# mx8m_dram.net
KiCad netlist of a schematic drawn in Altium Designer
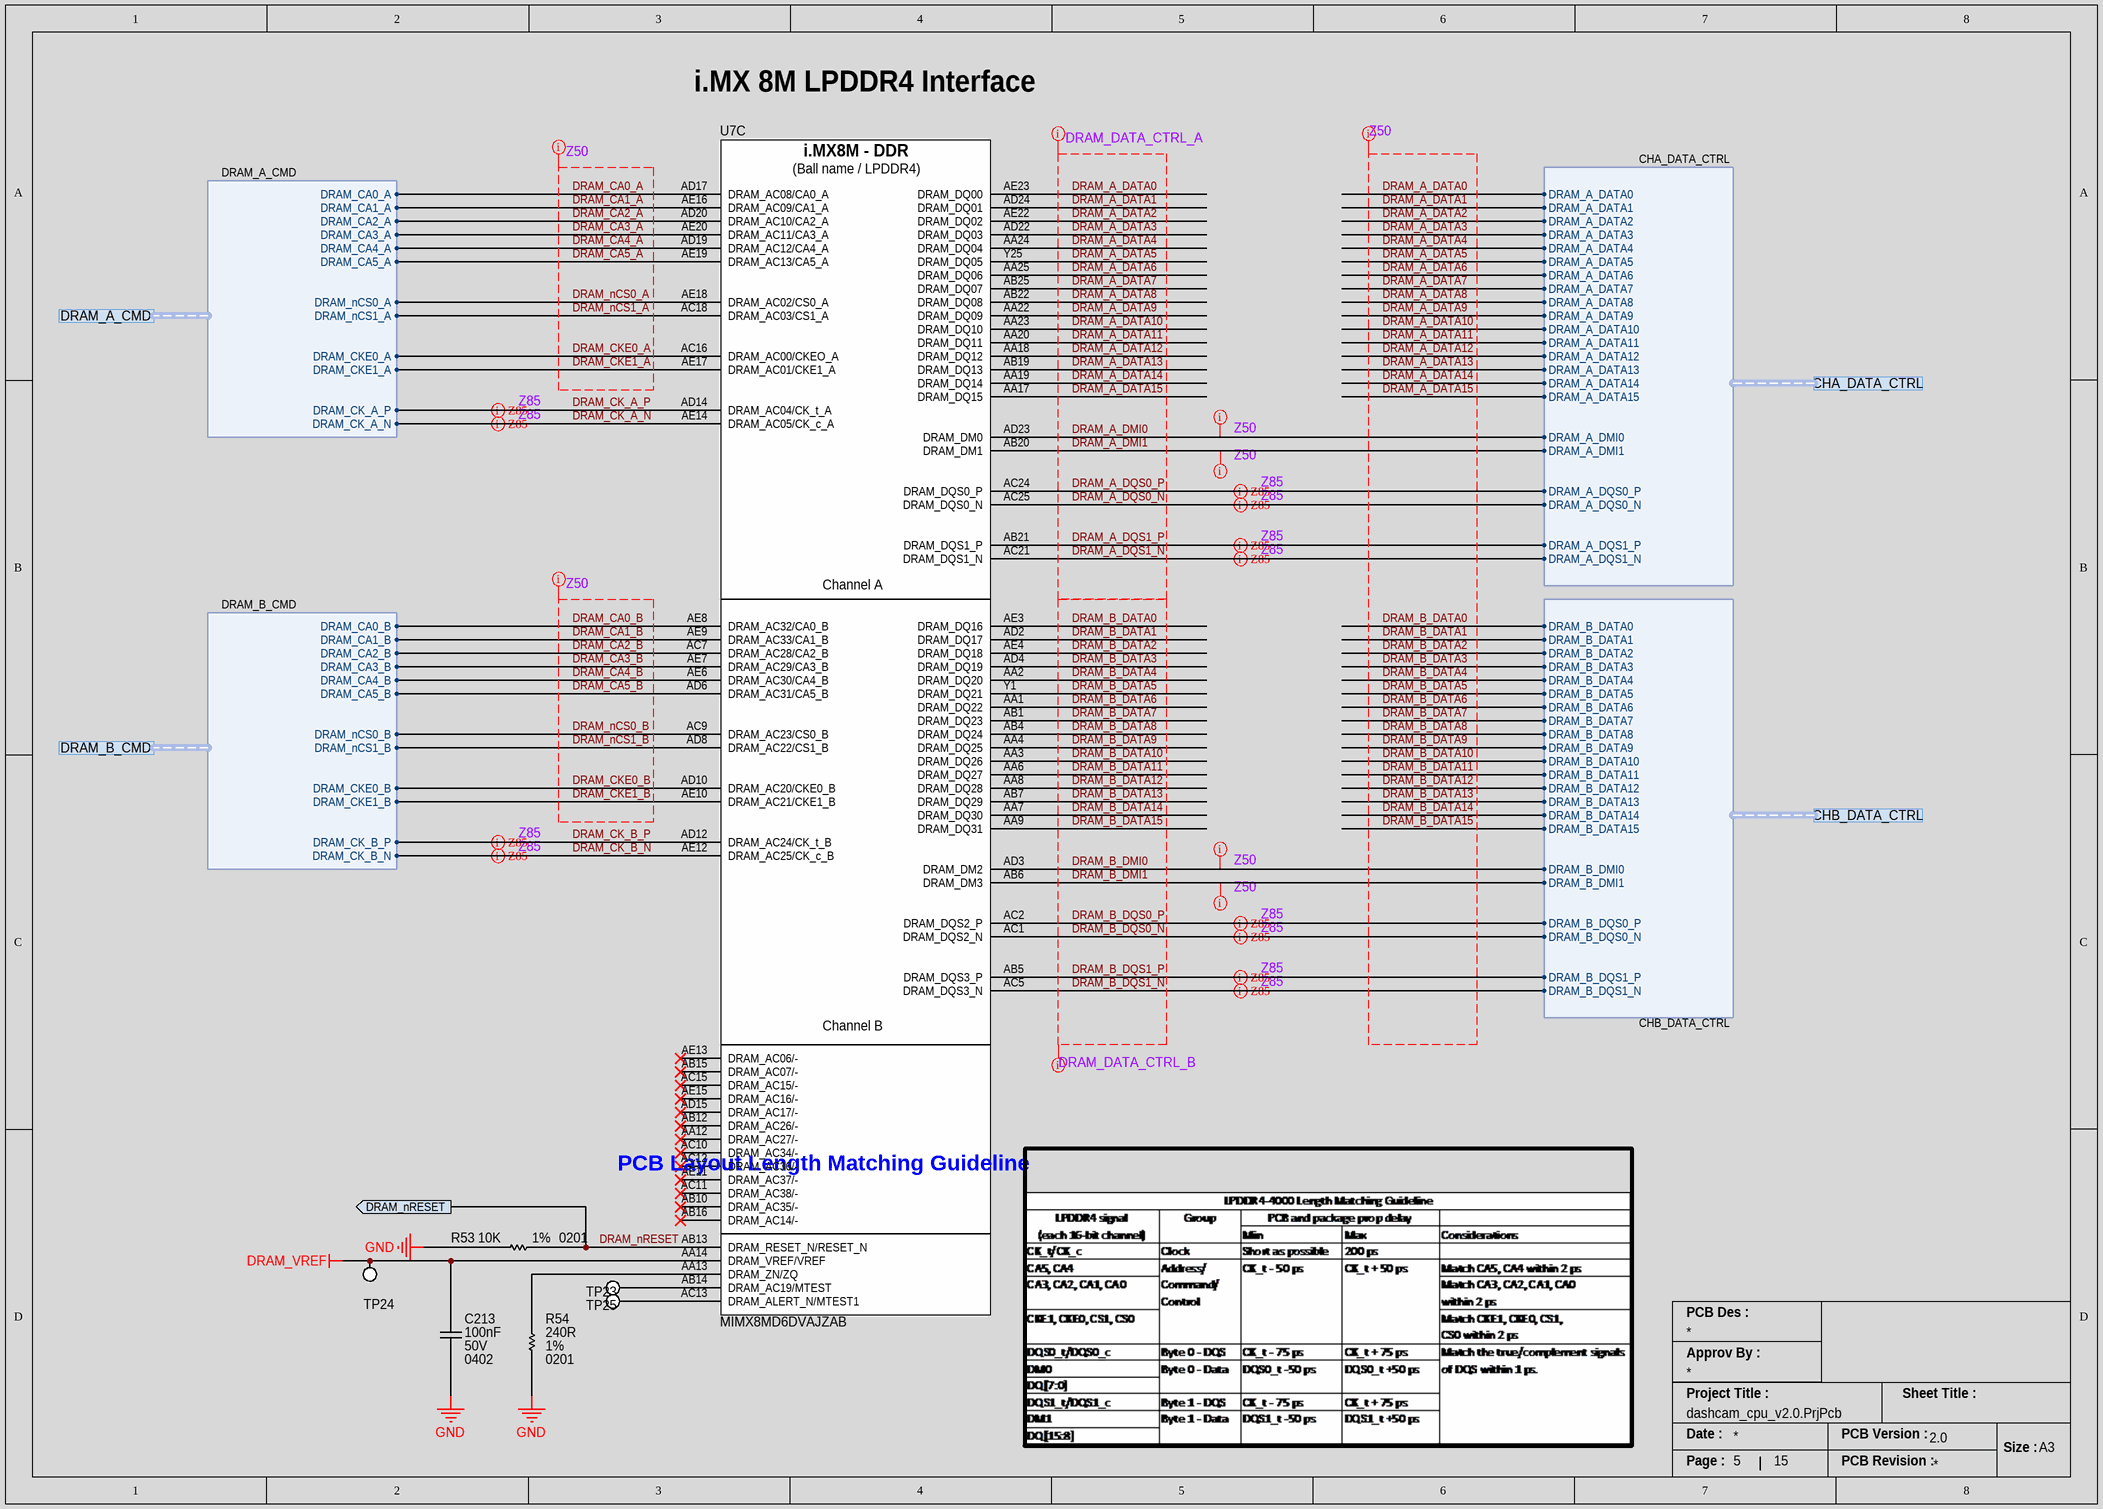
[diagram p0: mx8m_dram.SchDoc]

(export (version "E")
  (design (tool "Eeschema 10.0.6"))
  (components
    (comp (ref "C213")
      (value "GRM155R71H104KE14D")
      (footprint "CAP_0402_CAPC1005X05N")
      (description "Multilayer Ceramic Capacitor, 0.1 uF, 16 V, ± 10%, X7R, 0402 [1005 Metric]")
      (fields
        (field (name "MANUFACTURER") "Murata")
        (field (name "TOLERANCE") "10%")
        (field (name "VOLTAGE RATING") "50V")
        (field (name "CAPACITANCE") "100nF")
        (field (name "CASE/PACKAGE") "0402")
      )
      (libsource (lib "Electronic Devices_LIB") (part "CAP_100NF_50V_X7R_0402"))
    )
    (comp (ref "R53")
      (value "RC0201FR-0710KL")
      (footprint "RES_0201_RESC0603X02N")
      (description "SMD Chip Resistor, 10 kOhm, ± 1%, 50 mW, 0201 [0603 Metric], Thick Film, General Purpose")
      (fields
        (field (name "MANUFACTURER") "Yageo")
        (field (name "TOLERANCE") "1%")
        (field (name "RESISTANCE") "10K")
        (field (name "CASE CODE (IMPERIAL)") "0201")
      )
      (libsource (lib "Electronic Devices_LIB") (part "RES_10K_1/12W_1%_0201"))
    )
    (comp (ref "R54")
      (value "RC0201FR-07240RL")
      (footprint "RES_0201_RESC0603X02N")
      (description "SMD Chip Resistor, 240 Ohm, ± 1%, 50 mW, 0201 [0603 Metric], Thick Film, General Purpose")
      (fields
        (field (name "MANUFACTURER") "Yageo")
        (field (name "TOLERANCE") "1%")
        (field (name "RESISTANCE") "240R")
        (field (name "CASE/PACKAGE") "0201")
      )
      (libsource (lib "Electronic Devices_LIB") (part "RES_240R_1%_50mW_0201"))
    )
    (comp (ref "TP23")
      (value "NO COMPONENT")
      (footprint "TP_PAD_1.6MM_SMD_ROUND")
      (description "Test Point, SMD pad, round, 1.5mm, 1.6mm, 3mm diameter")
      (libsource (lib "Electronic Devices_LIB") (part "TP_PAD_SMD_Round"))
    )
    (comp (ref "TP24")
      (value "NO COMPONENT")
      (footprint "TP_PAD_1.6MM_SMD_ROUND")
      (description "Test Point, SMD pad, round, 1.5mm, 1.6mm, 3mm diameter")
      (libsource (lib "Electronic Devices_LIB") (part "TP_PAD_SMD_Round"))
    )
    (comp (ref "TP25")
      (value "NO COMPONENT")
      (footprint "TP_PAD_1.6MM_SMD_ROUND")
      (description "Test Point, SMD pad, round, 1.5mm, 1.6mm, 3mm diameter")
      (libsource (lib "Electronic Devices_LIB") (part "TP_PAD_SMD_Round"))
    )
    (comp (ref "U7")
      (value "MIMX8MD6DVAJZAB")
      (footprint "IC_MPU_BGA621C65P25X25_1700X1700X218")
      (fields (field (name "MANUFACTURER") "NXP Semiconductors"))
      (libsource (lib "Electronic Devices_LIB") (part "IC_MPU_ARM_1.5GHZ_MIMX8MD6DVAJZAB"))
    )
  )
  (nets
    (net (code "5") (name "/DRAM_A_DATA0") (class "Default")
      (node (ref "U7") (pin "AE23") (pinfunction "DRAM_DQ00_AE23") (pintype "passive"))
    )
    (net (code "6") (name "/DRAM_A_DATA1") (class "Default")
      (node (ref "U7") (pin "AD24") (pinfunction "DRAM_DQ01_AD24") (pintype "passive"))
    )
    (net (code "7") (name "/DRAM_A_DATA2") (class "Default")
      (node (ref "U7") (pin "AE22") (pinfunction "DRAM_DQ02_AE22") (pintype "passive"))
    )
    (net (code "8") (name "/DRAM_A_DATA3") (class "Default")
      (node (ref "U7") (pin "AD22") (pinfunction "DRAM_DQ03_AD22") (pintype "passive"))
    )
    (net (code "9") (name "/DRAM_A_DATA4") (class "Default")
      (node (ref "U7") (pin "AA24") (pinfunction "DRAM_DQ04_AA24") (pintype "passive"))
    )
    (net (code "10") (name "/DRAM_A_DATA5") (class "Default")
      (node (ref "U7") (pin "Y25") (pinfunction "DRAM_DQ05_Y25") (pintype "passive"))
    )
    (net (code "11") (name "/DRAM_A_DATA6") (class "Default")
      (node (ref "U7") (pin "AA25") (pinfunction "DRAM_DQ06_AA25") (pintype "passive"))
    )
    (net (code "12") (name "/DRAM_A_DATA7") (class "Default")
      (node (ref "U7") (pin "AB25") (pinfunction "DRAM_DQ07_AB25") (pintype "passive"))
    )
    (net (code "13") (name "/DRAM_A_DATA8") (class "Default")
      (node (ref "U7") (pin "AB22") (pinfunction "DRAM_DQ08_AB22") (pintype "passive"))
    )
    (net (code "14") (name "/DRAM_A_DATA9") (class "Default")
      (node (ref "U7") (pin "AA22") (pinfunction "DRAM_DQ09_AA22") (pintype "passive"))
    )
    (net (code "15") (name "/DRAM_A_DATA10") (class "Default")
      (node (ref "U7") (pin "AA23") (pinfunction "DRAM_DQ10_AA23") (pintype "passive"))
    )
    (net (code "16") (name "/DRAM_A_DATA11") (class "Default")
      (node (ref "U7") (pin "AA20") (pinfunction "DRAM_DQ11_AA20") (pintype "passive"))
    )
    (net (code "17") (name "/DRAM_A_DATA12") (class "Default")
      (node (ref "U7") (pin "AA18") (pinfunction "DRAM_DQ12_AA18") (pintype "passive"))
    )
    (net (code "18") (name "/DRAM_A_DATA13") (class "Default")
      (node (ref "U7") (pin "AB19") (pinfunction "DRAM_DQ13_AB19") (pintype "passive"))
    )
    (net (code "19") (name "/DRAM_A_DATA14") (class "Default")
      (node (ref "U7") (pin "AA19") (pinfunction "DRAM_DQ14_AA19") (pintype "passive"))
    )
    (net (code "20") (name "/DRAM_A_DATA15") (class "Default")
      (node (ref "U7") (pin "AA17") (pinfunction "DRAM_DQ15_AA17") (pintype "passive"))
    )
    (net (code "21") (name "/DRAM_A_DMI0") (class "Default")
      (node (ref "U7") (pin "AD23") (pinfunction "DRAM_DM0_AD23") (pintype "passive"))
    )
    (net (code "22") (name "/DRAM_A_DMI1") (class "Default")
      (node (ref "U7") (pin "AB20") (pinfunction "DRAM_DM1_AB20") (pintype "passive"))
    )
    (net (code "23") (name "/DRAM_A_DQS0_N") (class "Default")
      (node (ref "U7") (pin "AC25") (pinfunction "DRAM_DQS0_N_AC25") (pintype "passive"))
    )
    (net (code "24") (name "/DRAM_A_DQS0_P") (class "Default")
      (node (ref "U7") (pin "AC24") (pinfunction "DRAM_DQS0_P_AC24") (pintype "passive"))
    )
    (net (code "25") (name "/DRAM_A_DQS1_N") (class "Default")
      (node (ref "U7") (pin "AC21") (pinfunction "DRAM_DQS1_N_AC21") (pintype "passive"))
    )
    (net (code "26") (name "/DRAM_A_DQS1_P") (class "Default")
      (node (ref "U7") (pin "AB21") (pinfunction "DRAM_DQS1_P_AB21") (pintype "passive"))
    )
    (net (code "27") (name "/DRAM_B_DATA0") (class "Default")
      (node (ref "U7") (pin "AE3") (pinfunction "DRAM_DQ16_AE3") (pintype "passive"))
    )
    (net (code "28") (name "/DRAM_B_DATA1") (class "Default")
      (node (ref "U7") (pin "AD2") (pinfunction "DRAM_DQ17_AD2") (pintype "passive"))
    )
    (net (code "29") (name "/DRAM_B_DATA2") (class "Default")
      (node (ref "U7") (pin "AE4") (pinfunction "DRAM_DQ18_AE4") (pintype "passive"))
    )
    (net (code "30") (name "/DRAM_B_DATA3") (class "Default")
      (node (ref "U7") (pin "AD4") (pinfunction "DRAM_DQ19_AD4") (pintype "passive"))
    )
    (net (code "31") (name "/DRAM_B_DATA4") (class "Default")
      (node (ref "U7") (pin "AA2") (pinfunction "DRAM_DQ20_AA2") (pintype "passive"))
    )
    (net (code "32") (name "/DRAM_B_DATA5") (class "Default")
      (node (ref "U7") (pin "Y1") (pinfunction "DRAM_DQ21_Y1") (pintype "passive"))
    )
    (net (code "33") (name "/DRAM_B_DATA6") (class "Default")
      (node (ref "U7") (pin "AA1") (pinfunction "DRAM_DQ22_AA1") (pintype "passive"))
    )
    (net (code "34") (name "/DRAM_B_DATA7") (class "Default")
      (node (ref "U7") (pin "AB1") (pinfunction "DRAM_DQ23_AB1") (pintype "passive"))
    )
    (net (code "35") (name "/DRAM_B_DATA8") (class "Default")
      (node (ref "U7") (pin "AB4") (pinfunction "DRAM_DQ24_AB4") (pintype "passive"))
    )
    (net (code "36") (name "/DRAM_B_DATA9") (class "Default")
      (node (ref "U7") (pin "AA4") (pinfunction "DRAM_DQ25_AA4") (pintype "passive"))
    )
    (net (code "37") (name "/DRAM_B_DATA10") (class "Default")
      (node (ref "U7") (pin "AA3") (pinfunction "DRAM_DQ26_AA3") (pintype "passive"))
    )
    (net (code "38") (name "/DRAM_B_DATA11") (class "Default")
      (node (ref "U7") (pin "AA6") (pinfunction "DRAM_DQ27_AA6") (pintype "passive"))
    )
    (net (code "39") (name "/DRAM_B_DATA12") (class "Default")
      (node (ref "U7") (pin "AA8") (pinfunction "DRAM_DQ28_AA8") (pintype "passive"))
    )
    (net (code "40") (name "/DRAM_B_DATA13") (class "Default")
      (node (ref "U7") (pin "AB7") (pinfunction "DRAM_DQ29_AB7") (pintype "passive"))
    )
    (net (code "41") (name "/DRAM_B_DATA14") (class "Default")
      (node (ref "U7") (pin "AA7") (pinfunction "DRAM_DQ30_AA7") (pintype "passive"))
    )
    (net (code "42") (name "/DRAM_B_DATA15") (class "Default")
      (node (ref "U7") (pin "AA9") (pinfunction "DRAM_DQ31_AA9") (pintype "passive"))
    )
    (net (code "43") (name "/DRAM_B_DMI0") (class "Default")
      (node (ref "U7") (pin "AD3") (pinfunction "DRAM_DM2_AD3") (pintype "passive"))
    )
    (net (code "44") (name "/DRAM_B_DMI1") (class "Default")
      (node (ref "U7") (pin "AB6") (pinfunction "DRAM_DM3_AB6") (pintype "passive"))
    )
    (net (code "45") (name "/DRAM_B_DQS0_N") (class "Default")
      (node (ref "U7") (pin "AC1") (pinfunction "DRAM_DQS2_N_AC1") (pintype "passive"))
    )
    (net (code "46") (name "/DRAM_B_DQS0_P") (class "Default")
      (node (ref "U7") (pin "AC2") (pinfunction "DRAM_DQS2_P_AC2") (pintype "passive"))
    )
    (net (code "47") (name "/DRAM_B_DQS1_N") (class "Default")
      (node (ref "U7") (pin "AC5") (pinfunction "DRAM_DQS3_N_AC5") (pintype "passive"))
    )
    (net (code "48") (name "/DRAM_B_DQS1_P") (class "Default")
      (node (ref "U7") (pin "AB5") (pinfunction "DRAM_DQS3_P_AB5") (pintype "passive"))
    )
    (net (code "49") (name "/DRAM_CA0_A") (class "Default")
      (node (ref "U7") (pin "AD17") (pinfunction "DRAM_AC08/CA0_A_AD17") (pintype "passive"))
    )
    (net (code "50") (name "/DRAM_CA0_B") (class "Default")
      (node (ref "U7") (pin "AE8") (pinfunction "DRAM_AC32/CA0_B_AE8") (pintype "passive"))
    )
    (net (code "51") (name "/DRAM_CA1_A") (class "Default")
      (node (ref "U7") (pin "AE16") (pinfunction "DRAM_AC09/CA1_A_AE16") (pintype "passive"))
    )
    (net (code "52") (name "/DRAM_CA1_B") (class "Default")
      (node (ref "U7") (pin "AE9") (pinfunction "DRAM_AC33/CA1_B_AE9") (pintype "passive"))
    )
    (net (code "53") (name "/DRAM_CA2_A") (class "Default")
      (node (ref "U7") (pin "AD20") (pinfunction "DRAM_AC10/CA2_A_AD20") (pintype "passive"))
    )
    (net (code "54") (name "/DRAM_CA2_B") (class "Default")
      (node (ref "U7") (pin "AC7") (pinfunction "DRAM_AC28/CA2_B_AC7") (pintype "passive"))
    )
    (net (code "55") (name "/DRAM_CA3_A") (class "Default")
      (node (ref "U7") (pin "AE20") (pinfunction "DRAM_AC11/CA3_A_AE20") (pintype "passive"))
    )
    (net (code "56") (name "/DRAM_CA3_B") (class "Default")
      (node (ref "U7") (pin "AE7") (pinfunction "DRAM_AC29/CA3_B_AE7") (pintype "passive"))
    )
    (net (code "57") (name "/DRAM_CA4_A") (class "Default")
      (node (ref "U7") (pin "AD19") (pinfunction "DRAM_AC12/CA4_A_AD19") (pintype "passive"))
    )
    (net (code "58") (name "/DRAM_CA4_B") (class "Default")
      (node (ref "U7") (pin "AE6") (pinfunction "DRAM_AC30/CA4_B_AE6") (pintype "passive"))
    )
    (net (code "59") (name "/DRAM_CA5_A") (class "Default")
      (node (ref "U7") (pin "AE19") (pinfunction "DRAM_AC13/CA5_A_AE19") (pintype "passive"))
    )
    (net (code "60") (name "/DRAM_CA5_B") (class "Default")
      (node (ref "U7") (pin "AD6") (pinfunction "DRAM_AC31/CA5_B_AD6") (pintype "passive"))
    )
    (net (code "61") (name "/DRAM_CKE0_A") (class "Default")
      (node (ref "U7") (pin "AC16") (pinfunction "DRAM_AC00/CKEO_A_AC16") (pintype "passive"))
    )
    (net (code "62") (name "/DRAM_CKE0_B") (class "Default")
      (node (ref "U7") (pin "AD10") (pinfunction "DRAM_AC20/CKE0_B_AD10") (pintype "passive"))
    )
    (net (code "63") (name "/DRAM_CKE1_A") (class "Default")
      (node (ref "U7") (pin "AE17") (pinfunction "DRAM_AC01/CKE1_A_AE17") (pintype "passive"))
    )
    (net (code "64") (name "/DRAM_CKE1_B") (class "Default")
      (node (ref "U7") (pin "AE10") (pinfunction "DRAM_AC21/CKE1_B_AE10") (pintype "passive"))
    )
    (net (code "65") (name "/DRAM_CK_A_N") (class "Default")
      (node (ref "U7") (pin "AE14") (pinfunction "DRAM_AC05/CK_c_A_AE14") (pintype "passive"))
    )
    (net (code "66") (name "/DRAM_CK_A_P") (class "Default")
      (node (ref "U7") (pin "AD14") (pinfunction "DRAM_AC04/CK_t_A_AD14") (pintype "passive"))
    )
    (net (code "67") (name "/DRAM_CK_B_N") (class "Default")
      (node (ref "U7") (pin "AE12") (pinfunction "DRAM_AC25/CK_c_B_AE12") (pintype "passive"))
    )
    (net (code "68") (name "/DRAM_CK_B_P") (class "Default")
      (node (ref "U7") (pin "AD12") (pinfunction "DRAM_AC24/CK_t_B_AD12") (pintype "passive"))
    )
    (net (code "69") (name "/DRAM_nCS0_A") (class "Default")
      (node (ref "U7") (pin "AE18") (pinfunction "DRAM_AC02/CS0_A_AE18") (pintype "passive"))
    )
    (net (code "70") (name "/DRAM_nCS0_B") (class "Default")
      (node (ref "U7") (pin "AC9") (pinfunction "DRAM_AC23/CS0_B_AC9") (pintype "passive"))
    )
    (net (code "71") (name "/DRAM_nCS1_A") (class "Default")
      (node (ref "U7") (pin "AC18") (pinfunction "DRAM_AC03/CS1_A_AC18") (pintype "passive"))
    )
    (net (code "72") (name "/DRAM_nCS1_B") (class "Default")
      (node (ref "U7") (pin "AD8") (pinfunction "DRAM_AC22/CS1_B_AD8") (pintype "passive"))
    )
    (net (code "73") (name "/DRAM_nRESET") (class "Default")
      (node (ref "R53") (pin "2") (pinfunction "2_2") (pintype "passive"))
      (node (ref "U7") (pin "AB13") (pinfunction "DRAM_RESET_N/RESET_N_AB13") (pintype "passive"))
    )
    (net (code "78") (name "DRAM_VREF") (class "Default")
      (node (ref "C213") (pin "2") (pinfunction "2_2") (pintype "passive"))
      (node (ref "TP24") (pin "1") (pinfunction "1_1") (pintype "passive"))
      (node (ref "U7") (pin "AA14") (pinfunction "DRAM_VREF/VREF_AA14") (pintype "passive"))
    )
    (net (code "79") (name "GND") (class "Default")
      (node (ref "C213") (pin "1") (pinfunction "1_1") (pintype "passive"))
      (node (ref "R53") (pin "1") (pinfunction "1_1") (pintype "passive"))
      (node (ref "R54") (pin "1") (pinfunction "1_1") (pintype "passive"))
    )
    (net (code "80") (name "Net-(U7C-DRAM_AC19{slash}MTEST)") (class "Default")
      (node (ref "TP23") (pin "1") (pinfunction "1_1") (pintype "passive"))
      (node (ref "U7") (pin "AB14") (pinfunction "DRAM_AC19/MTEST_AB14") (pintype "passive"))
    )
    (net (code "81") (name "Net-(U7C-DRAM_ALERT_N{slash}MTEST1)") (class "Default")
      (node (ref "TP25") (pin "1") (pinfunction "1_1") (pintype "passive"))
      (node (ref "U7") (pin "AC13") (pinfunction "DRAM_ALERT_N/MTEST1_AC13") (pintype "passive"))
    )
    (net (code "82") (name "Net-(U7C-DRAM_ZN{slash}ZQ)") (class "Default")
      (node (ref "R54") (pin "2") (pinfunction "2_2") (pintype "passive"))
      (node (ref "U7") (pin "AA13") (pinfunction "DRAM_ZN/ZQ_AA13") (pintype "passive"))
    )
    (net (code "83") (name "unconnected-(U7C-DRAM_AC06{slash}--PadAE13)") (class "Default")
      (node (ref "U7") (pin "AE13") (pinfunction "DRAM_AC06/-_AE13") (pintype "passive+no_connect"))
    )
    (net (code "84") (name "unconnected-(U7C-DRAM_AC07{slash}--PadAB15)") (class "Default")
      (node (ref "U7") (pin "AB15") (pinfunction "DRAM_AC07/-_AB15") (pintype "passive+no_connect"))
    )
    (net (code "85") (name "unconnected-(U7C-DRAM_AC14{slash}--PadAB16)") (class "Default")
      (node (ref "U7") (pin "AB16") (pinfunction "DRAM_AC14/-_AB16") (pintype "passive+no_connect"))
    )
    (net (code "86") (name "unconnected-(U7C-DRAM_AC15{slash}--PadAC15)") (class "Default")
      (node (ref "U7") (pin "AC15") (pinfunction "DRAM_AC15/-_AC15") (pintype "passive+no_connect"))
    )
    (net (code "87") (name "unconnected-(U7C-DRAM_AC16{slash}--PadAE15)") (class "Default")
      (node (ref "U7") (pin "AE15") (pinfunction "DRAM_AC16/-_AE15") (pintype "passive+no_connect"))
    )
    (net (code "88") (name "unconnected-(U7C-DRAM_AC17{slash}--PadAD15)") (class "Default")
      (node (ref "U7") (pin "AD15") (pinfunction "DRAM_AC17/-_AD15") (pintype "passive+no_connect"))
    )
    (net (code "89") (name "unconnected-(U7C-DRAM_AC26{slash}--PadAB12)") (class "Default")
      (node (ref "U7") (pin "AB12") (pinfunction "DRAM_AC26/-_AB12") (pintype "passive+no_connect"))
    )
    (net (code "90") (name "unconnected-(U7C-DRAM_AC27{slash}--PadAA12)") (class "Default")
      (node (ref "U7") (pin "AA12") (pinfunction "DRAM_AC27/-_AA12") (pintype "passive+no_connect"))
    )
    (net (code "91") (name "unconnected-(U7C-DRAM_AC34{slash}--PadAC10)") (class "Default")
      (node (ref "U7") (pin "AC10") (pinfunction "DRAM_AC34/-_AC10") (pintype "passive+no_connect"))
    )
    (net (code "92") (name "unconnected-(U7C-DRAM_AC35{slash}--PadAB10)") (class "Default")
      (node (ref "U7") (pin "AB10") (pinfunction "DRAM_AC35/-_AB10") (pintype "passive+no_connect"))
    )
    (net (code "93") (name "unconnected-(U7C-DRAM_AC36{slash}--PadAC12)") (class "Default")
      (node (ref "U7") (pin "AC12") (pinfunction "DRAM_AC36/-_AC12") (pintype "passive+no_connect"))
    )
    (net (code "94") (name "unconnected-(U7C-DRAM_AC37{slash}--PadAE11)") (class "Default")
      (node (ref "U7") (pin "AE11") (pinfunction "DRAM_AC37/-_AE11") (pintype "passive+no_connect"))
    )
    (net (code "95") (name "unconnected-(U7C-DRAM_AC38{slash}--PadAC11)") (class "Default")
      (node (ref "U7") (pin "AC11") (pinfunction "DRAM_AC38/-_AC11") (pintype "passive+no_connect"))
    )
  )
)
